# PowerV3.net
KiCad netlist of a schematic drawn in Altium Designer
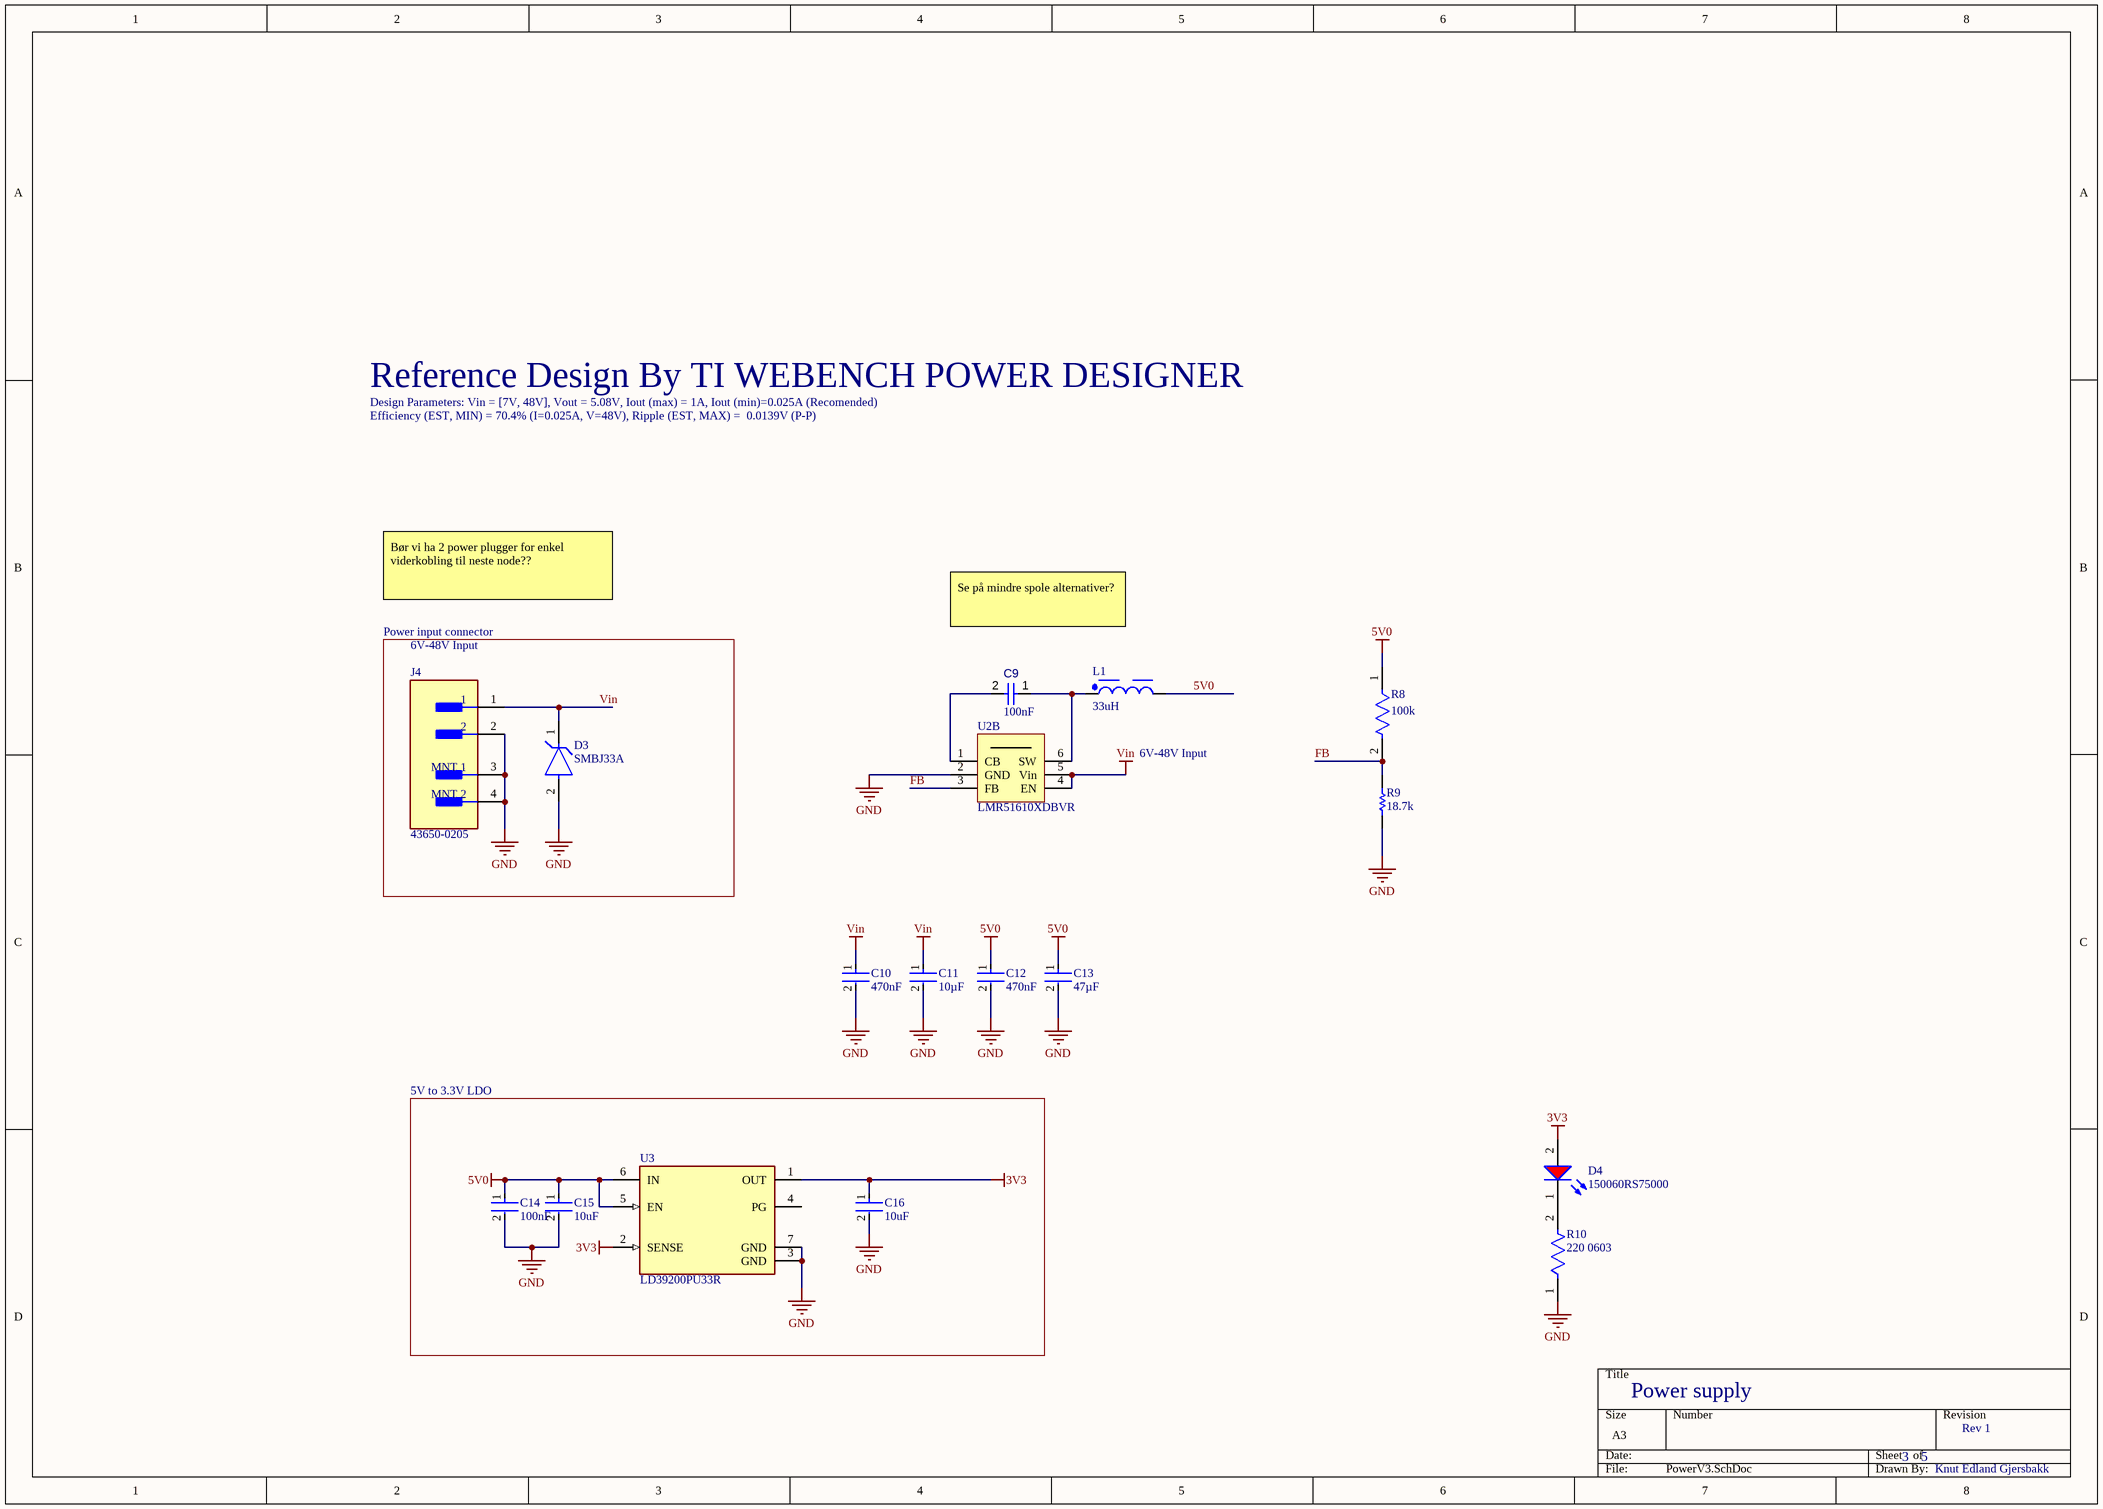
[diagram p0: PowerV3.SchDoc]

(export (version "E")
  (design (tool "Eeschema 10.0.6"))
  (components
    (comp (ref "C9")
      (value "100nF")
      (footprint "CAPC2013X95X50LL10T25")
      (description "Chip Capacitor, 100 nF, +/- 10%, 50 V, 0805 (2012 Metric)")
      (fields (field (name "TOLERANCE") "10%") (field (name "Comment") "Capacitor 100 nF +/-10% 50 V 0805"))
      (libsource (lib "UiS Aerospace") (part "CAP-NP-2"))
    )
    (comp (ref "C10")
      (value "470nF")
      (footprint "FP-CL21-IPC_A")
      (fields (field (name "Comment") "CL21B474KBFNNNF"))
      (libsource (lib "UiS Aerospace") (part "b4654b650e69147ec39a6b967a45e02"))
    )
    (comp (ref "C11")
      (value "10µF")
      (footprint "FP-CL31B106KBHNNNE-IPC_A")
      (fields (field (name "Comment") "CL31B106KBHNNNE"))
      (libsource (lib "UiS Aerospace") (part "b4654b650e69147ec39a6b967a45e02"))
    )
    (comp (ref "C12")
      (value "470nF")
      (footprint "FP-CL21-IPC_A")
      (fields (field (name "Comment") "CL21B474KBFNNNF"))
      (libsource (lib "UiS Aerospace") (part "b4654b650e69147ec39a6b967a45e02"))
    )
    (comp (ref "C13")
      (value "47µF")
      (footprint "FP-GRM31C-0_2-e0_3_0_8-IPC_B")
      (fields (field (name "Comment") "GRM31CR61A476KE15K"))
      (libsource (lib "UiS Aerospace") (part "02cd4be3c70576c341d710602a673aa"))
    )
    (comp (ref "C14")
      (value "100nF")
      (footprint "FP-CL10-IPC_C")
      (description "Cap Ceramic 100nF 16V X7R ±10% Pad SMD 0603 +125°C T/R\r\nCL10B104KO8WPNC")
      (fields (field (name "TOLERANCE") "10%"))
      (libsource (lib "Altium Content Vault") (part "b4654b650e69147ec39a6b967a45e02"))
    )
    (comp (ref "C15")
      (value "10uF")
      (footprint "FP-CL10-IPC_C")
      (description "Cap Ceramic 10uF 16V X6S ±20% Pad SMD 0603 +105°C T/R\r\nCL10X106MO8NRNC")
      (fields (field (name "TOLERANCE") "20%"))
      (libsource (lib "Altium Content Vault") (part "b4654b650e69147ec39a6b967a45e02"))
    )
    (comp (ref "C16")
      (value "10uF")
      (footprint "FP-CL10-IPC_C")
      (description "Cap Ceramic 10uF 16V X6S ±20% Pad SMD 0603 +105°C T/R\r\nCL10X106MO8NRNC")
      (fields (field (name "TOLERANCE") "20%"))
      (libsource (lib "Altium Content Vault") (part "b4654b650e69147ec39a6b967a45e02"))
    )
    (comp (ref "D3")
      (value "SMBJ33A")
      (footprint "FP-SMBJ-MFG")
      (description "TVS DIODE 33V 53.3V DO214AA")
      (fields
        (field (name "MANUFACTURER") "Littelfuse Inc")
        (field (name "OCTOPART") "https://octopart.com/smbj33a-littelfuse-350829")
      )
      (libsource (lib "Altium Content Vault") (part "f813f71cba58e380607f5dd3caf9714"))
    )
    (comp (ref "D4")
      (value "150060RS75000")
      (footprint "WL-SMCW_0603_150060xx75000")
      (description "LED Low-Power Uni-Color Red 630nm 2V 2-Pin Chip 0603(1608Metric) T/R")
      (libsource (lib "Altium Content Vault") (part "LED_Red_2A-1K"))
    )
    (comp (ref "J4")
      (value "43650-0205")
      (footprint "FP-43650-0205-MFG")
      (description "43650-0205 Conn Wire to Board HDR 2 POS 3mm Solder RA Side Entry Thru-Hole Micro-Fit 3.0™ Tray")
      (libsource (lib "Altium Content Vault") (part "56ec3178a87b3978bdc1b3682cd516a"))
    )
    (comp (ref "L1")
      (value "33uH")
      (footprint "WE-PD_1260P")
      (description "General Purpose Inductor")
      (fields (field (name "Comment") "7447706330"))
      (libsource (lib "UiS Aerospace") (part "Inductor - 2"))
    )
    (comp (ref "R8")
      (value "100k")
      (footprint "FP-CRGCQ1206-IPC_A")
      (fields (field (name "Comment") "CRGCQ1206F100K"))
      (libsource (lib "UiS Aerospace") (part "1029c3af85768c4190bb7ad29bc67b5"))
    )
    (comp (ref "R9")
      (value "18.7k")
      (footprint "RESC2013X60X40LL20T25")
      (description "Fixed Resistor, Thin Film, 0.125W, 18700ohm, 100V, 0.1% +/-Tol, 25ppm/Cel, Surface Mount, 0805")
      (fields (field (name "TOLERANCE") "0.1%") (field (name "POWER") "125mW"))
      (libsource (lib "UiS Aerospace") (part "RES"))
    )
    (comp (ref "R10")
      (value "220 0603")
      (footprint "FP-AF0603-IPC_C")
      (description "AF0603JR-07220RL Anti-Sulfurated Chip Resistors Automotive Grade 220Ω 5% 100ppm/°C 0603")
      (fields (field (name "TOLERANCE") "5%"))
      (libsource (lib "Altium Content Vault") (part "1029c3af85768c4190bb7ad29bc67b5"))
    )
    (comp (ref "U2")
      (value "LMR51610XDBVR")
      (footprint "SOT95P280X145-6N")
      (description "SIMPLE SWITCHER® 4.5-V to 65-V, 1-A synchronous buck converter with 25-µA IQ 6-SOT-23 -40 to 150")
      (libsource (lib "UiS Aerospace") (part "LMR51610XDBVR-Symbol-1"))
    )
    (comp (ref "U3")
      (value "LD39200PU33R")
      (footprint "FP-DFN6-7946637-MFG")
      (description "IC REG LINEAR 3.3V 2A 6DFN")
      (libsource (lib "Altium Content Vault") (part "f0cfe00d12cb984572f50007c934a2d"))
    )
  )
  (nets
    (net (code "1") (name "/FB") (class "Default")
      (node (ref "R8") (pin "2") (pinfunction "2_2") (pintype "passive"))
      (node (ref "R9") (pin "1") (pinfunction "1_1") (pintype "passive"))
      (node (ref "U2") (pin "3") (pinfunction "FB_3") (pintype "passive"))
    )
    (net (code "2") (name "3V3") (class "Default")
      (node (ref "C16") (pin "1") (pinfunction "1_1") (pintype "passive"))
      (node (ref "D4") (pin "2") (pinfunction "A_2") (pintype "passive"))
      (node (ref "U3") (pin "1") (pinfunction "OUT_1") (pintype "power_in"))
      (node (ref "U3") (pin "2") (pinfunction "SENSE_2") (pintype "input"))
    )
    (net (code "3") (name "5V0") (class "Default")
      (node (ref "C12") (pin "1") (pinfunction "1_1") (pintype "passive"))
      (node (ref "C13") (pin "1") (pinfunction "1_1") (pintype "passive"))
      (node (ref "C14") (pin "1") (pinfunction "1_1") (pintype "passive"))
      (node (ref "C15") (pin "1") (pinfunction "1_1") (pintype "passive"))
      (node (ref "L1") (pin "2") (pinfunction "2_2") (pintype "passive"))
      (node (ref "R8") (pin "1") (pinfunction "1_1") (pintype "passive"))
      (node (ref "U3") (pin "5") (pinfunction "EN_5") (pintype "input"))
      (node (ref "U3") (pin "6") (pinfunction "IN_6") (pintype "power_in"))
    )
    (net (code "4") (name "GND") (class "Default")
      (node (ref "C10") (pin "2") (pinfunction "2_2") (pintype "passive"))
      (node (ref "C11") (pin "2") (pinfunction "2_2") (pintype "passive"))
      (node (ref "C12") (pin "2") (pinfunction "2_2") (pintype "passive"))
      (node (ref "C13") (pin "2") (pinfunction "2_2") (pintype "passive"))
      (node (ref "C14") (pin "2") (pinfunction "2_2") (pintype "passive"))
      (node (ref "C15") (pin "2") (pinfunction "2_2") (pintype "passive"))
      (node (ref "C16") (pin "2") (pinfunction "2_2") (pintype "passive"))
      (node (ref "D3") (pin "2") (pinfunction "A_2") (pintype "passive"))
      (node (ref "J4") (pin "2") (pinfunction "2_2") (pintype "passive"))
      (node (ref "J4") (pin "3") (pinfunction "MNT_1_3") (pintype "passive"))
      (node (ref "J4") (pin "4") (pinfunction "MNT_2_4") (pintype "passive"))
      (node (ref "R10") (pin "1") (pinfunction "1_1") (pintype "passive"))
      (node (ref "R9") (pin "2") (pinfunction "2_2") (pintype "passive"))
      (node (ref "U2") (pin "2") (pinfunction "GND_2") (pintype "passive"))
      (node (ref "U3") (pin "3") (pinfunction "GND_3") (pintype "power_in"))
      (node (ref "U3") (pin "7") (pinfunction "GND_7") (pintype "power_in"))
    )
    (net (code "5") (name "Net-(D4-K)") (class "Default")
      (node (ref "D4") (pin "1") (pinfunction "K_1") (pintype "passive"))
      (node (ref "R10") (pin "2") (pinfunction "2_2") (pintype "passive"))
    )
    (net (code "6") (name "Net-(U2B-CB)") (class "Default")
      (node (ref "C9") (pin "2") (pinfunction "2_2") (pintype "passive"))
      (node (ref "U2") (pin "1") (pinfunction "CB_1") (pintype "passive"))
    )
    (net (code "7") (name "Net-(U2B-SW)") (class "Default")
      (node (ref "C9") (pin "1") (pinfunction "1_1") (pintype "passive"))
      (node (ref "L1") (pin "1") (pinfunction "1_1") (pintype "passive"))
      (node (ref "U2") (pin "6") (pinfunction "SW_6") (pintype "passive"))
    )
    (net (code "8") (name "Vin") (class "Default")
      (node (ref "C10") (pin "1") (pinfunction "1_1") (pintype "passive"))
      (node (ref "C11") (pin "1") (pinfunction "1_1") (pintype "passive"))
      (node (ref "D3") (pin "1") (pinfunction "C_1") (pintype "passive"))
      (node (ref "J4") (pin "1") (pinfunction "1_1") (pintype "passive"))
      (node (ref "U2") (pin "4") (pinfunction "EN_4") (pintype "passive"))
      (node (ref "U2") (pin "5") (pinfunction "Vin_5") (pintype "passive"))
    )
    (net (code "9") (name "unconnected-(U3-PG-Pad4)") (class "Default")
      (node (ref "U3") (pin "4") (pinfunction "PG_4") (pintype "open_collector"))
    )
  )
)
